# 04_-Connector.net
KiCad netlist of a schematic drawn in Altium Designer
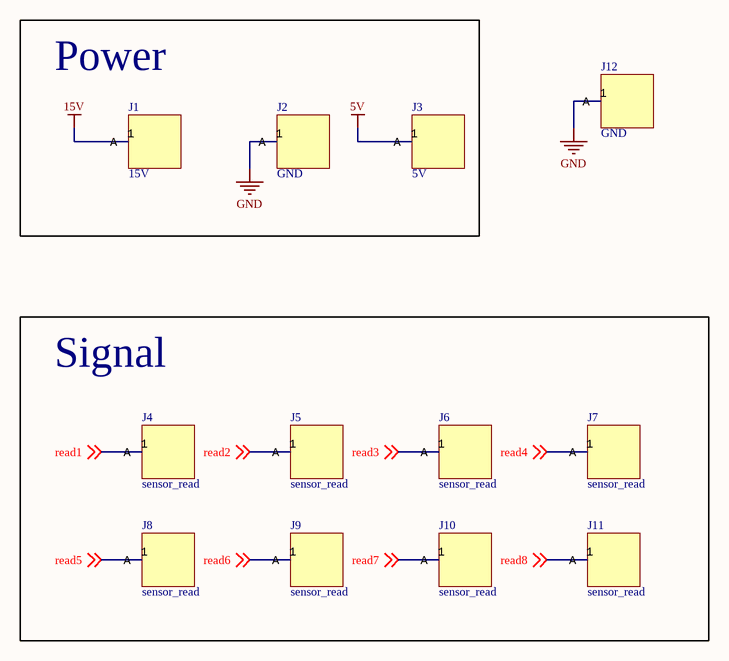
[diagram p0: [04]-Connector.SchDoc]

(export (version "E")
  (design (tool "Eeschema 10.0.6"))
  (components
    (comp (ref "J1") (value "15V") (footprint "PIN") (libsource (lib "Schlib1") (part "15V")))
    (comp (ref "J2") (value "GND") (footprint "PIN") (libsource (lib "Schlib1") (part "GND")))
    (comp (ref "J3") (value "5V") (footprint "PIN") (libsource (lib "Schlib1") (part "15V")))
    (comp (ref "J4") (value "sensor_read") (footprint "PIN") (libsource (lib "Schlib1") (part "sensor_read")))
    (comp (ref "J5") (value "sensor_read") (footprint "PIN") (libsource (lib "Schlib1") (part "sensor_read")))
    (comp (ref "J6") (value "sensor_read") (footprint "PIN") (libsource (lib "Schlib1") (part "sensor_read")))
    (comp (ref "J7") (value "sensor_read") (footprint "PIN") (libsource (lib "Schlib1") (part "sensor_read")))
    (comp (ref "J8") (value "sensor_read") (footprint "PIN") (libsource (lib "Schlib1") (part "sensor_read")))
    (comp (ref "J9") (value "sensor_read") (footprint "PIN") (libsource (lib "Schlib1") (part "sensor_read")))
    (comp (ref "J10")
      (value "sensor_read")
      (footprint "PIN")
      (libsource (lib "Schlib1") (part "sensor_read"))
    )
    (comp (ref "J11")
      (value "sensor_read")
      (footprint "PIN")
      (libsource (lib "Schlib1") (part "sensor_read"))
    )
    (comp (ref "J12") (value "GND") (footprint "PIN") (libsource (lib "Schlib1") (part "GND")))
  )
  (nets
    (net (code "1") (name "5V") (class "Default")
      (node (ref "J3") (pin "1") (pinfunction "A_1") (pintype "passive"))
    )
    (net (code "2") (name "15V") (class "Default")
      (node (ref "J1") (pin "1") (pinfunction "A_1") (pintype "passive"))
    )
    (net (code "3") (name "GND") (class "Default")
      (node (ref "J12") (pin "1") (pinfunction "A_1") (pintype "passive"))
      (node (ref "J2") (pin "1") (pinfunction "A_1") (pintype "passive"))
    )
    (net (code "4") (name "read1") (class "Default")
      (node (ref "J4") (pin "1") (pinfunction "A_1") (pintype "passive"))
    )
    (net (code "5") (name "read2") (class "Default")
      (node (ref "J5") (pin "1") (pinfunction "A_1") (pintype "passive"))
    )
    (net (code "6") (name "read3") (class "Default")
      (node (ref "J6") (pin "1") (pinfunction "A_1") (pintype "passive"))
    )
    (net (code "7") (name "read4") (class "Default")
      (node (ref "J7") (pin "1") (pinfunction "A_1") (pintype "passive"))
    )
    (net (code "8") (name "read5") (class "Default")
      (node (ref "J8") (pin "1") (pinfunction "A_1") (pintype "passive"))
    )
    (net (code "9") (name "read6") (class "Default")
      (node (ref "J9") (pin "1") (pinfunction "A_1") (pintype "passive"))
    )
    (net (code "10") (name "read7") (class "Default")
      (node (ref "J10") (pin "1") (pinfunction "A_1") (pintype "passive"))
    )
    (net (code "11") (name "read8") (class "Default")
      (node (ref "J11") (pin "1") (pinfunction "A_1") (pintype "passive"))
    )
  )
)
